# BottleBuddy-V1_2.net
KiCad netlist of a schematic drawn in EAGLE
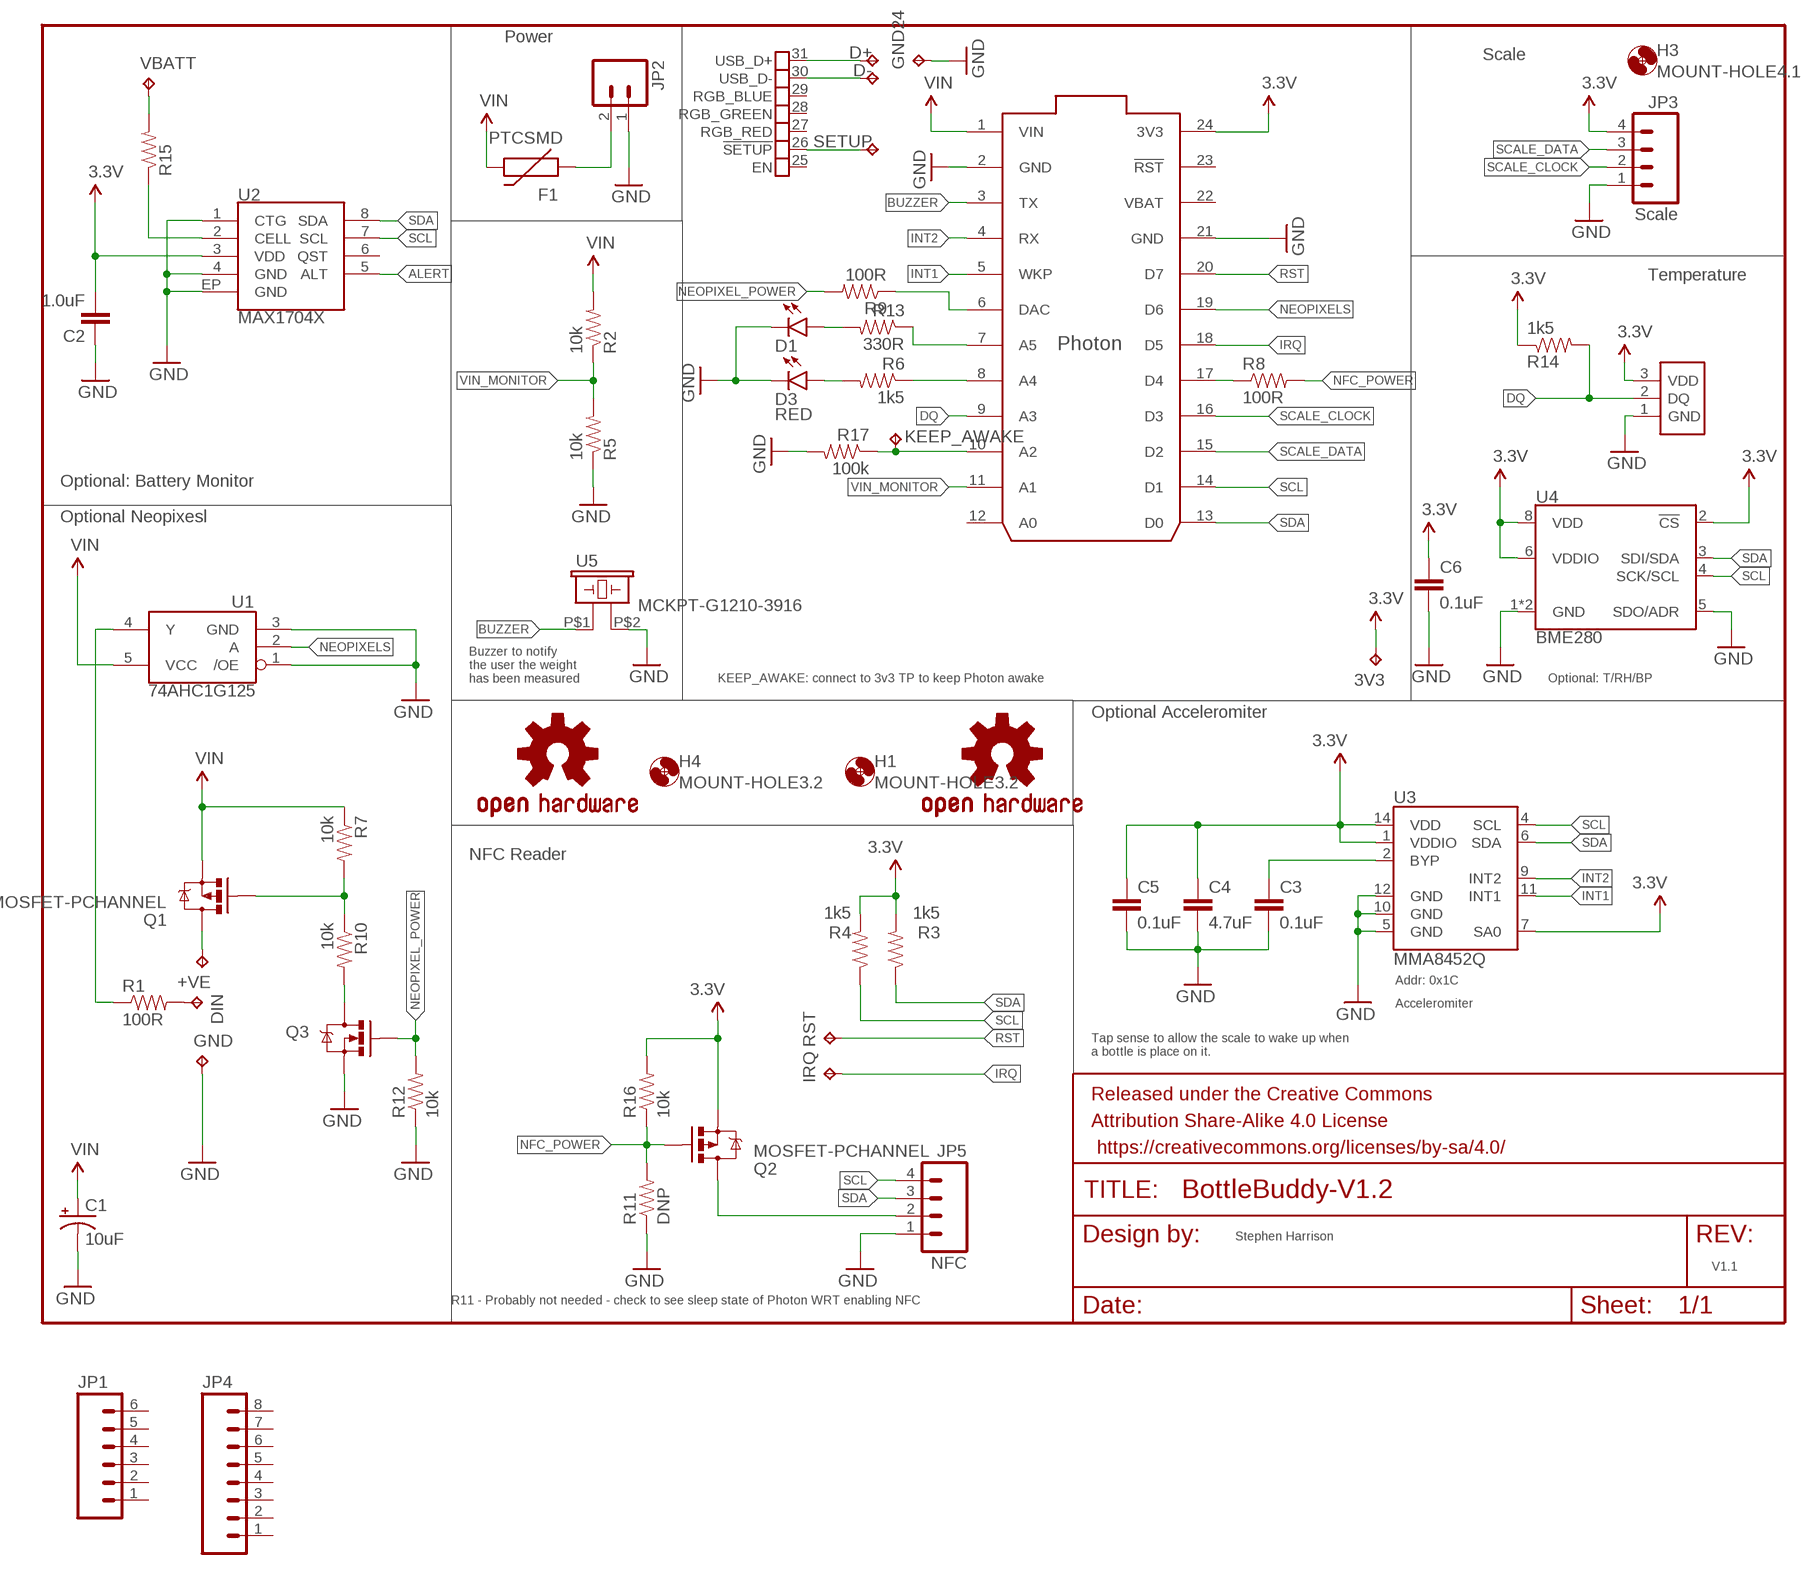
[diagram p0: schematic, sheet 1]

(export (version "E")
  (design (tool "Eeschema 10.0.6"))
  (components
    (comp (ref "+VE")
      (value "TPTP20R")
      (footprint "eagle-import:TP20R")
      (libsource (lib "eagle-import") (part "TPTP20R"))
    )
    (comp (ref "3V3")
      (value "TPTP20R")
      (footprint "eagle-import:TP20R")
      (libsource (lib "eagle-import") (part "TPTP20R"))
    )
    (comp (ref "C1")
      (value "10uF")
      (footprint "eagle-import:EIA3216")
      (libsource (lib "eagle-import") (part "10UF-16V-10%(TANT)"))
    )
    (comp (ref "C2")
      (value "1.0uF")
      (footprint "eagle-import:0805-CAP")
      (libsource (lib "eagle-import") (part "1.0UF-25V-+80/-20(0805){dblquote}"))
    )
    (comp (ref "C3")
      (value "0.1uF")
      (footprint "eagle-import:0805")
      (libsource (lib "eagle-import") (part "CAP0805"))
    )
    (comp (ref "C4")
      (value "4.7uF")
      (footprint "eagle-import:0805")
      (libsource (lib "eagle-import") (part "CAP0805"))
    )
    (comp (ref "C5")
      (value "0.1uF")
      (footprint "eagle-import:0805")
      (libsource (lib "eagle-import") (part "CAP0805"))
    )
    (comp (ref "C6")
      (value "0.1uF")
      (footprint "eagle-import:0805")
      (libsource (lib "eagle-import") (part "CAP0805"))
    )
    (comp (ref "D+")
      (value "TPTP20R")
      (footprint "eagle-import:TP20R")
      (libsource (lib "eagle-import") (part "TPTP20R"))
    )
    (comp (ref "D-")
      (value "TPTP20R")
      (footprint "eagle-import:TP20R")
      (libsource (lib "eagle-import") (part "TPTP20R"))
    )
    (comp (ref "D1")
      (value "LED1206-BOTTOM")
      (footprint "eagle-import:LED-1206-BOTTOM")
      (libsource (lib "eagle-import") (part "LED1206-BOTTOM"))
    )
    (comp (ref "D3")
      (value "RED")
      (footprint "eagle-import:LED-1206")
      (libsource (lib "eagle-import") (part "LED1206"))
    )
    (comp (ref "DIN")
      (value "TPTP20R")
      (footprint "eagle-import:TP20R")
      (libsource (lib "eagle-import") (part "TPTP20R"))
    )
    (comp (ref "F1")
      (value "PTCSMD")
      (footprint "eagle-import:PTC-1206")
      (libsource (lib "eagle-import") (part "PTCSMD"))
    )
    (comp (ref "FRAME1")
      (value "FRAME-LETTER")
      (footprint "eagle-import:CREATIVE_COMMONS")
      (libsource (lib "eagle-import") (part "FRAME-LETTER"))
    )
    (comp (ref "GND")
      (value "TPTP20R")
      (footprint "eagle-import:TP20R")
      (libsource (lib "eagle-import") (part "TPTP20R"))
    )
    (comp (ref "GND24")
      (value "TPTP20R")
      (footprint "eagle-import:TP20R")
      (libsource (lib "eagle-import") (part "TPTP20R"))
    )
    (comp (ref "H1")
      (value "MOUNT-HOLE3.2")
      (footprint "eagle-import:3,2")
      (libsource (lib "eagle-import") (part "MOUNT-HOLE3.2"))
    )
    (comp (ref "H3")
      (value "MOUNT-HOLE4.1")
      (footprint "eagle-import:4,1")
      (libsource (lib "eagle-import") (part "MOUNT-HOLE4.1"))
    )
    (comp (ref "H4")
      (value "MOUNT-HOLE3.2")
      (footprint "eagle-import:3,2")
      (libsource (lib "eagle-import") (part "MOUNT-HOLE3.2"))
    )
    (comp (ref "IRQ")
      (value "NFC IRQ")
      (footprint "eagle-import:TP20R")
      (libsource (lib "eagle-import") (part "TPTP20R"))
    )
    (comp (ref "JP1")
      (value "M06SILK_FEMALE_PTH")
      (footprint "eagle-import:1X06")
      (libsource (lib "eagle-import") (part "M06SILK_FEMALE_PTH"))
    )
    (comp (ref "JP2")
      (value "M02-JST-2MM-SMT")
      (footprint "eagle-import:JST-2-SMD")
      (libsource (lib "eagle-import") (part "M02-JST-2MM-SMT"))
    )
    (comp (ref "JP3")
      (value "Scale")
      (footprint "eagle-import:1X04")
      (libsource (lib "eagle-import") (part "M04PTH"))
    )
    (comp (ref "JP4")
      (value "M08SILK_FEMALE_PTH")
      (footprint "eagle-import:1X08")
      (libsource (lib "eagle-import") (part "M08SILK_FEMALE_PTH"))
    )
    (comp (ref "JP5")
      (value "NFC")
      (footprint "eagle-import:1X04")
      (libsource (lib "eagle-import") (part "M04PTH"))
    )
    (comp (ref "KEEP_AWAKE")
      (value "TPTP20R")
      (footprint "eagle-import:TP20R")
      (libsource (lib "eagle-import") (part "TPTP20R"))
    )
    (comp (ref "LOGO1")
      (value "OSHW-LOGOL")
      (footprint "eagle-import:OSHW-LOGO-L")
      (libsource (lib "eagle-import") (part "OSHW-LOGOL"))
    )
    (comp (ref "LOGO2")
      (value "OSHW-LOGOL")
      (footprint "eagle-import:OSHW-LOGO-L")
      (libsource (lib "eagle-import") (part "OSHW-LOGOL"))
    )
    (comp (ref "Q1")
      (value "MOSFET-PCHANNEL")
      (footprint "eagle-import:SOT23-3")
      (libsource (lib "eagle-import") (part "MOSFET-PCHANNEL"))
    )
    (comp (ref "Q2")
      (value "MOSFET-PCHANNEL")
      (footprint "eagle-import:SOT23-3")
      (libsource (lib "eagle-import") (part "MOSFET-PCHANNEL"))
    )
    (comp (ref "Q3")
      (value "200mA/50V")
      (footprint "eagle-import:SOT23-3")
      (libsource (lib "eagle-import") (part "MOSFET-NCHANNELBSS138"))
    )
    (comp (ref "R1")
      (value "100R")
      (footprint "eagle-import:1206")
      (libsource (lib "eagle-import") (part "RESISTOR1206"))
    )
    (comp (ref "R2")
      (value "10k")
      (footprint "eagle-import:1206")
      (libsource (lib "eagle-import") (part "RESISTOR1206"))
    )
    (comp (ref "R3")
      (value "1k5")
      (footprint "eagle-import:1206")
      (libsource (lib "eagle-import") (part "RESISTOR1206"))
    )
    (comp (ref "R4")
      (value "1k5")
      (footprint "eagle-import:1206")
      (libsource (lib "eagle-import") (part "RESISTOR1206"))
    )
    (comp (ref "R5")
      (value "10k")
      (footprint "eagle-import:1206")
      (libsource (lib "eagle-import") (part "RESISTOR1206"))
    )
    (comp (ref "R6")
      (value "1k5")
      (footprint "eagle-import:1206")
      (libsource (lib "eagle-import") (part "RESISTOR1206"))
    )
    (comp (ref "R7")
      (value "10k")
      (footprint "eagle-import:1206")
      (libsource (lib "eagle-import") (part "RESISTOR1206"))
    )
    (comp (ref "R8")
      (value "100R")
      (footprint "eagle-import:1206")
      (libsource (lib "eagle-import") (part "RESISTOR1206"))
    )
    (comp (ref "R9")
      (value "100R")
      (footprint "eagle-import:1206")
      (libsource (lib "eagle-import") (part "RESISTOR1206"))
    )
    (comp (ref "R10")
      (value "10k")
      (footprint "eagle-import:1206")
      (libsource (lib "eagle-import") (part "RESISTOR1206"))
    )
    (comp (ref "R11")
      (value "DNP")
      (footprint "eagle-import:1206")
      (libsource (lib "eagle-import") (part "RESISTOR1206"))
    )
    (comp (ref "R12")
      (value "10k")
      (footprint "eagle-import:1206")
      (libsource (lib "eagle-import") (part "RESISTOR1206"))
    )
    (comp (ref "R13")
      (value "330R")
      (footprint "eagle-import:1206")
      (libsource (lib "eagle-import") (part "RESISTOR1206"))
    )
    (comp (ref "R14")
      (value "1k5")
      (footprint "eagle-import:1206")
      (libsource (lib "eagle-import") (part "RESISTOR1206"))
    )
    (comp (ref "R15")
      (value "RESISTOR1206")
      (footprint "eagle-import:1206")
      (libsource (lib "eagle-import") (part "RESISTOR1206"))
    )
    (comp (ref "R16")
      (value "10k")
      (footprint "eagle-import:1206")
      (libsource (lib "eagle-import") (part "RESISTOR1206"))
    )
    (comp (ref "R17")
      (value "100k")
      (footprint "eagle-import:1206")
      (libsource (lib "eagle-import") (part "RESISTOR1206"))
    )
    (comp (ref "RST")
      (value "TPTP20R")
      (footprint "eagle-import:TP20R")
      (libsource (lib "eagle-import") (part "TPTP20R"))
    )
    (comp (ref "S1")
      (value "SENSOR-DS18B20")
      (footprint "eagle-import:TO-92-TRIANGLE")
      (libsource (lib "eagle-import") (part "SENSOR-DS18B20"))
    )
    (comp (ref "SETUP")
      (value "TPTP20R")
      (footprint "eagle-import:TP20R")
      (libsource (lib "eagle-import") (part "TPTP20R"))
    )
    (comp (ref "U$1")
      (value "PHOTON_SMD")
      (footprint "eagle-import:PHOTON_SMD")
      (libsource (lib "eagle-import") (part "PHOTON_SMD"))
    )
    (comp (ref "U1")
      (value "74AHC1G125")
      (footprint "eagle-import:SOT23-5")
      (libsource (lib "eagle-import") (part "74AHC1G125"))
    )
    (comp (ref "U2")
      (value "MAX1704X")
      (footprint "eagle-import:TDFN-8")
      (libsource (lib "eagle-import") (part "MAX1704X"))
    )
    (comp (ref "U3")
      (value "MMA8452Q")
      (footprint "eagle-import:QFN-16_0.5MM")
      (libsource (lib "eagle-import") (part "MMA8452Q"))
    )
    (comp (ref "U4")
      (value "BME280")
      (footprint "eagle-import:LGA-8-2.5X2.5")
      (libsource (lib "eagle-import") (part "BME280"))
    )
    (comp (ref "U5")
      (value "MCKPT-G1210-3916")
      (footprint "eagle-import:BUZZER-12MM")
      (libsource (lib "eagle-import") (part "MCKPT-G1210-3916"))
    )
    (comp (ref "VBATT")
      (value "TPTP20R")
      (footprint "eagle-import:TP20R")
      (libsource (lib "eagle-import") (part "TPTP20R"))
    )
  )
  (nets
    (net (code "1") (name "/VBAT") (class "Default")
      (node (ref "U$1") (pin "22") (pinfunction "VBAT_22") (pintype "power_in"))
    )
    (net (code "2") (name "3.3V") (class "Default")
      (node (ref "3V3") (pin "TP") (pinfunction "TP_TP") (pintype "input"))
      (node (ref "C2") (pin "2") (pinfunction "2_2") (pintype "passive"))
      (node (ref "C4") (pin "1") (pinfunction "1_1") (pintype "passive"))
      (node (ref "C5") (pin "1") (pinfunction "1_1") (pintype "passive"))
      (node (ref "C6") (pin "1") (pinfunction "1_1") (pintype "passive"))
      (node (ref "JP3") (pin "4") (pinfunction "4_4") (pintype "passive"))
      (node (ref "Q2") (pin "2") (pinfunction "S_2") (pintype "passive"))
      (node (ref "R14") (pin "1") (pinfunction "1_1") (pintype "passive"))
      (node (ref "R16") (pin "2") (pinfunction "2_2") (pintype "passive"))
      (node (ref "R3") (pin "2") (pinfunction "2_2") (pintype "passive"))
      (node (ref "R4") (pin "2") (pinfunction "2_2") (pintype "passive"))
      (node (ref "S1") (pin "3") (pinfunction "VDD_3") (pintype "bidirectional"))
      (node (ref "U$1") (pin "24") (pinfunction "3V3_24") (pintype "power_in"))
      (node (ref "U2") (pin "3") (pinfunction "VDD_3") (pintype "bidirectional"))
      (node (ref "U3") (pin "1") (pinfunction "VDDIO_1") (pintype "bidirectional"))
      (node (ref "U3") (pin "14") (pinfunction "VDD_14") (pintype "bidirectional"))
      (node (ref "U3") (pin "7") (pinfunction "SA0_7") (pintype "bidirectional"))
      (node (ref "U4") (pin "2") (pinfunction "~{CS}_2") (pintype "bidirectional"))
      (node (ref "U4") (pin "6") (pinfunction "VDDIO_6") (pintype "bidirectional"))
      (node (ref "U4") (pin "8") (pinfunction "VDD_8") (pintype "bidirectional"))
    )
    (net (code "3") (name "ALERT") (class "Default")
      (node (ref "U2") (pin "5") (pinfunction "ALT_5") (pintype "bidirectional"))
    )
    (net (code "4") (name "BUZZER") (class "Default")
      (node (ref "U$1") (pin "3") (pinfunction "TX_3") (pintype "bidirectional"))
      (node (ref "U5") (pin "P$1") (pinfunction "1_P$1") (pintype "passive"))
    )
    (net (code "5") (name "DQ") (class "Default")
      (node (ref "R14") (pin "2") (pinfunction "2_2") (pintype "passive"))
      (node (ref "S1") (pin "2") (pinfunction "DQ_2") (pintype "bidirectional"))
      (node (ref "U$1") (pin "9") (pinfunction "A3_9") (pintype "bidirectional"))
    )
    (net (code "6") (name "GND") (class "Default")
      (node (ref "C1") (pin "C") (pinfunction "-_C") (pintype "passive"))
      (node (ref "C2") (pin "1") (pinfunction "1_1") (pintype "passive"))
      (node (ref "C3") (pin "2") (pinfunction "2_2") (pintype "passive"))
      (node (ref "C4") (pin "2") (pinfunction "2_2") (pintype "passive"))
      (node (ref "C5") (pin "2") (pinfunction "2_2") (pintype "passive"))
      (node (ref "C6") (pin "2") (pinfunction "2_2") (pintype "passive"))
      (node (ref "D1") (pin "C") (pinfunction "C_C") (pintype "passive"))
      (node (ref "D3") (pin "C") (pinfunction "C_C") (pintype "passive"))
      (node (ref "GND") (pin "TP") (pinfunction "TP_TP") (pintype "input"))
      (node (ref "GND24") (pin "TP") (pinfunction "TP_TP") (pintype "input"))
      (node (ref "JP2") (pin "1") (pinfunction "2_1") (pintype "passive"))
      (node (ref "JP3") (pin "1") (pinfunction "1_1") (pintype "passive"))
      (node (ref "JP5") (pin "1") (pinfunction "1_1") (pintype "passive"))
      (node (ref "Q3") (pin "2") (pinfunction "S_2") (pintype "passive"))
      (node (ref "R11") (pin "1") (pinfunction "1_1") (pintype "passive"))
      (node (ref "R12") (pin "1") (pinfunction "1_1") (pintype "passive"))
      (node (ref "R17") (pin "2") (pinfunction "2_2") (pintype "passive"))
      (node (ref "R5") (pin "1") (pinfunction "1_1") (pintype "passive"))
      (node (ref "S1") (pin "1") (pinfunction "GND_1") (pintype "bidirectional"))
      (node (ref "U$1") (pin "2") (pinfunction "GND_2") (pintype "power_in"))
      (node (ref "U$1") (pin "21") (pinfunction "GND_21") (pintype "power_in"))
      (node (ref "U1") (pin "1") (pinfunction "/OE_1") (pintype "bidirectional"))
      (node (ref "U1") (pin "3") (pinfunction "GND_3") (pintype "bidirectional"))
      (node (ref "U2") (pin "1") (pinfunction "CTG_1") (pintype "bidirectional"))
      (node (ref "U2") (pin "4") (pinfunction "GND_4") (pintype "bidirectional"))
      (node (ref "U2") (pin "EP") (pinfunction "GND_EP") (pintype "bidirectional"))
      (node (ref "U3") (pin "10") (pinfunction "GND_10") (pintype "bidirectional"))
      (node (ref "U3") (pin "12") (pinfunction "GND_12") (pintype "bidirectional"))
      (node (ref "U3") (pin "5") (pinfunction "GND_5") (pintype "bidirectional"))
      (node (ref "U4") (pin "1") (pinfunction "GND_1") (pintype "bidirectional"))
      (node (ref "U4") (pin "5") (pinfunction "SDO/ADR_5") (pintype "bidirectional"))
      (node (ref "U4") (pin "7") (pinfunction "GND_7") (pintype "bidirectional"))
      (node (ref "U5") (pin "P$2") (pinfunction "2_P$2") (pintype "passive"))
    )
    (net (code "7") (name "INT1") (class "Default")
      (node (ref "U$1") (pin "5") (pinfunction "WKP_5") (pintype "bidirectional"))
      (node (ref "U3") (pin "11") (pinfunction "INT1_11") (pintype "bidirectional"))
    )
    (net (code "8") (name "INT2") (class "Default")
      (node (ref "U$1") (pin "4") (pinfunction "RX_4") (pintype "bidirectional"))
      (node (ref "U3") (pin "9") (pinfunction "INT2_9") (pintype "bidirectional"))
    )
    (net (code "9") (name "IRQ") (class "Default")
      (node (ref "IRQ") (pin "TP") (pinfunction "TP_TP") (pintype "input"))
      (node (ref "U$1") (pin "18") (pinfunction "D5_18") (pintype "bidirectional"))
    )
    (net (code "10") (name "NEOPIXELS") (class "Default")
      (node (ref "U$1") (pin "19") (pinfunction "D6_19") (pintype "bidirectional"))
      (node (ref "U1") (pin "2") (pinfunction "A_2") (pintype "bidirectional"))
    )
    (net (code "11") (name "NEOPIXEL_POWER") (class "Default")
      (node (ref "Q3") (pin "1") (pinfunction "G_1") (pintype "passive"))
      (node (ref "R12") (pin "2") (pinfunction "2_2") (pintype "passive"))
      (node (ref "R9") (pin "2") (pinfunction "2_2") (pintype "passive"))
    )
    (net (code "12") (name "NFC_POWER") (class "Default")
      (node (ref "Q2") (pin "1") (pinfunction "G_1") (pintype "passive"))
      (node (ref "R11") (pin "2") (pinfunction "2_2") (pintype "passive"))
      (node (ref "R16") (pin "1") (pinfunction "1_1") (pintype "passive"))
      (node (ref "R8") (pin "2") (pinfunction "2_2") (pintype "passive"))
    )
    (net (code "13") (name "Net-(D1-PadA)") (class "Default")
      (node (ref "D1") (pin "A") (pinfunction "A_A") (pintype "passive"))
      (node (ref "R13") (pin "2") (pinfunction "2_2") (pintype "passive"))
    )
    (net (code "14") (name "Net-(D3-PadA)") (class "Default")
      (node (ref "D3") (pin "A") (pinfunction "A_A") (pintype "passive"))
      (node (ref "R6") (pin "2") (pinfunction "2_2") (pintype "passive"))
    )
    (net (code "15") (name "Net-(DIN-PadTP)") (class "Default")
      (node (ref "DIN") (pin "TP") (pinfunction "TP_TP") (pintype "input"))
      (node (ref "R1") (pin "2") (pinfunction "2_2") (pintype "passive"))
    )
    (net (code "16") (name "Net-(JP2-1)") (class "Default")
      (node (ref "F1") (pin "1") (pinfunction "1_1") (pintype "bidirectional"))
      (node (ref "JP2") (pin "2") (pinfunction "1_2") (pintype "passive"))
    )
    (net (code "17") (name "Net-(Q1-D)") (class "Default")
      (node (ref "+VE") (pin "TP") (pinfunction "TP_TP") (pintype "input"))
      (node (ref "Q1") (pin "3") (pinfunction "D_3") (pintype "passive"))
    )
    (net (code "18") (name "Net-(Q1-G)") (class "Default")
      (node (ref "Q1") (pin "1") (pinfunction "G_1") (pintype "passive"))
      (node (ref "R10") (pin "1") (pinfunction "1_1") (pintype "passive"))
      (node (ref "R7") (pin "2") (pinfunction "2_2") (pintype "passive"))
    )
    (net (code "19") (name "Net-(Q2-D)") (class "Default")
      (node (ref "JP5") (pin "2") (pinfunction "2_2") (pintype "passive"))
      (node (ref "Q2") (pin "3") (pinfunction "D_3") (pintype "passive"))
    )
    (net (code "20") (name "Net-(Q3-D)") (class "Default")
      (node (ref "Q3") (pin "3") (pinfunction "D_3") (pintype "passive"))
      (node (ref "R10") (pin "2") (pinfunction "2_2") (pintype "passive"))
    )
    (net (code "21") (name "Net-(R15-Pad2)") (class "Default")
      (node (ref "R15") (pin "2") (pinfunction "2_2") (pintype "passive"))
      (node (ref "VBATT") (pin "TP") (pinfunction "TP_TP") (pintype "input"))
    )
    (net (code "22") (name "Net-(U$1A-A2)") (class "Default")
      (node (ref "KEEP_AWAKE") (pin "TP") (pinfunction "TP_TP") (pintype "input"))
      (node (ref "R17") (pin "1") (pinfunction "1_1") (pintype "passive"))
      (node (ref "U$1") (pin "10") (pinfunction "A2_10") (pintype "bidirectional"))
    )
    (net (code "23") (name "Net-(U$1A-A4)") (class "Default")
      (node (ref "R6") (pin "1") (pinfunction "1_1") (pintype "passive"))
      (node (ref "U$1") (pin "8") (pinfunction "A4_8") (pintype "bidirectional"))
    )
    (net (code "24") (name "Net-(U$1A-A5)") (class "Default")
      (node (ref "R13") (pin "1") (pinfunction "1_1") (pintype "passive"))
      (node (ref "U$1") (pin "7") (pinfunction "A5_7") (pintype "bidirectional"))
    )
    (net (code "25") (name "Net-(U$1A-D4)") (class "Default")
      (node (ref "R8") (pin "1") (pinfunction "1_1") (pintype "passive"))
      (node (ref "U$1") (pin "17") (pinfunction "D4_17") (pintype "bidirectional"))
    )
    (net (code "26") (name "Net-(U$1A-DAC)") (class "Default")
      (node (ref "R9") (pin "1") (pinfunction "1_1") (pintype "passive"))
      (node (ref "U$1") (pin "6") (pinfunction "DAC_6") (pintype "bidirectional"))
    )
    (net (code "27") (name "Net-(U$1B-USB_D+)") (class "Default")
      (node (ref "D+") (pin "TP") (pinfunction "TP_TP") (pintype "input"))
      (node (ref "U$1") (pin "31") (pinfunction "USB_D+_31") (pintype "bidirectional"))
    )
    (net (code "28") (name "Net-(U$1B-USB_D-)") (class "Default")
      (node (ref "D-") (pin "TP") (pinfunction "TP_TP") (pintype "input"))
      (node (ref "U$1") (pin "30") (pinfunction "USB_D-_30") (pintype "bidirectional"))
    )
    (net (code "29") (name "Net-(U$1B-~{SETUP})") (class "Default")
      (node (ref "SETUP") (pin "TP") (pinfunction "TP_TP") (pintype "input"))
      (node (ref "U$1") (pin "26") (pinfunction "~{SETUP}_26") (pintype "bidirectional"))
    )
    (net (code "30") (name "Net-(U1-Y)") (class "Default")
      (node (ref "R1") (pin "1") (pinfunction "1_1") (pintype "passive"))
      (node (ref "U1") (pin "4") (pinfunction "Y_4") (pintype "bidirectional"))
    )
    (net (code "31") (name "Net-(U2-CELL)") (class "Default")
      (node (ref "R15") (pin "1") (pinfunction "1_1") (pintype "passive"))
      (node (ref "U2") (pin "2") (pinfunction "CELL_2") (pintype "bidirectional"))
    )
    (net (code "32") (name "Net-(U3-BYP)") (class "Default")
      (node (ref "C3") (pin "1") (pinfunction "1_1") (pintype "passive"))
      (node (ref "U3") (pin "2") (pinfunction "BYP_2") (pintype "bidirectional"))
    )
    (net (code "33") (name "RST") (class "Default")
      (node (ref "RST") (pin "TP") (pinfunction "TP_TP") (pintype "input"))
      (node (ref "U$1") (pin "20") (pinfunction "D7_20") (pintype "bidirectional"))
    )
    (net (code "34") (name "SCALE_CLOCK") (class "Default")
      (node (ref "JP3") (pin "2") (pinfunction "2_2") (pintype "passive"))
      (node (ref "U$1") (pin "16") (pinfunction "D3_16") (pintype "bidirectional"))
    )
    (net (code "35") (name "SCALE_DATA") (class "Default")
      (node (ref "JP3") (pin "3") (pinfunction "3_3") (pintype "passive"))
      (node (ref "U$1") (pin "15") (pinfunction "D2_15") (pintype "bidirectional"))
    )
    (net (code "36") (name "SCL") (class "Default")
      (node (ref "JP5") (pin "4") (pinfunction "4_4") (pintype "passive"))
      (node (ref "R4") (pin "1") (pinfunction "1_1") (pintype "passive"))
      (node (ref "U$1") (pin "14") (pinfunction "D1_14") (pintype "bidirectional"))
      (node (ref "U2") (pin "7") (pinfunction "SCL_7") (pintype "bidirectional"))
      (node (ref "U3") (pin "4") (pinfunction "SCL_4") (pintype "bidirectional"))
      (node (ref "U4") (pin "4") (pinfunction "SCK/SCL_4") (pintype "bidirectional"))
    )
    (net (code "37") (name "SDA") (class "Default")
      (node (ref "JP5") (pin "3") (pinfunction "3_3") (pintype "passive"))
      (node (ref "R3") (pin "1") (pinfunction "1_1") (pintype "passive"))
      (node (ref "U$1") (pin "13") (pinfunction "D0_13") (pintype "bidirectional"))
      (node (ref "U2") (pin "8") (pinfunction "SDA_8") (pintype "bidirectional"))
      (node (ref "U3") (pin "6") (pinfunction "SDA_6") (pintype "bidirectional"))
      (node (ref "U4") (pin "3") (pinfunction "SDI/SDA_3") (pintype "bidirectional"))
    )
    (net (code "38") (name "VIN") (class "Default")
      (node (ref "C1") (pin "A") (pinfunction "+_A") (pintype "passive"))
      (node (ref "F1") (pin "2") (pinfunction "2_2") (pintype "bidirectional"))
      (node (ref "Q1") (pin "2") (pinfunction "S_2") (pintype "passive"))
      (node (ref "R2") (pin "2") (pinfunction "2_2") (pintype "passive"))
      (node (ref "R7") (pin "1") (pinfunction "1_1") (pintype "passive"))
      (node (ref "U$1") (pin "1") (pinfunction "VIN_1") (pintype "power_in"))
      (node (ref "U1") (pin "5") (pinfunction "VCC_5") (pintype "bidirectional"))
    )
    (net (code "39") (name "VIN_MONITOR") (class "Default")
      (node (ref "R2") (pin "1") (pinfunction "1_1") (pintype "passive"))
      (node (ref "R5") (pin "2") (pinfunction "2_2") (pintype "passive"))
      (node (ref "U$1") (pin "11") (pinfunction "A1_11") (pintype "bidirectional"))
    )
    (net (code "40") (name "unconnected-(JP1-Pad1)") (class "Default")
      (node (ref "JP1") (pin "1") (pinfunction "1_1") (pintype "passive"))
    )
    (net (code "41") (name "unconnected-(JP1-Pad2)") (class "Default")
      (node (ref "JP1") (pin "2") (pinfunction "2_2") (pintype "passive"))
    )
    (net (code "42") (name "unconnected-(JP1-Pad3)") (class "Default")
      (node (ref "JP1") (pin "3") (pinfunction "3_3") (pintype "passive"))
    )
    (net (code "43") (name "unconnected-(JP1-Pad4)") (class "Default")
      (node (ref "JP1") (pin "4") (pinfunction "4_4") (pintype "passive"))
    )
    (net (code "44") (name "unconnected-(JP1-Pad5)") (class "Default")
      (node (ref "JP1") (pin "5") (pinfunction "5_5") (pintype "passive"))
    )
    (net (code "45") (name "unconnected-(JP1-Pad6)") (class "Default")
      (node (ref "JP1") (pin "6") (pinfunction "6_6") (pintype "passive"))
    )
    (net (code "46") (name "unconnected-(JP4-Pad1)") (class "Default")
      (node (ref "JP4") (pin "1") (pinfunction "1_1") (pintype "passive"))
    )
    (net (code "47") (name "unconnected-(JP4-Pad2)") (class "Default")
      (node (ref "JP4") (pin "2") (pinfunction "2_2") (pintype "passive"))
    )
    (net (code "48") (name "unconnected-(JP4-Pad3)") (class "Default")
      (node (ref "JP4") (pin "3") (pinfunction "3_3") (pintype "passive"))
    )
    (net (code "49") (name "unconnected-(JP4-Pad4)") (class "Default")
      (node (ref "JP4") (pin "4") (pinfunction "4_4") (pintype "passive"))
    )
    (net (code "50") (name "unconnected-(JP4-Pad5)") (class "Default")
      (node (ref "JP4") (pin "5") (pinfunction "5_5") (pintype "passive"))
    )
    (net (code "51") (name "unconnected-(JP4-Pad6)") (class "Default")
      (node (ref "JP4") (pin "6") (pinfunction "6_6") (pintype "passive"))
    )
    (net (code "52") (name "unconnected-(JP4-Pad7)") (class "Default")
      (node (ref "JP4") (pin "7") (pinfunction "7_7") (pintype "passive"))
    )
    (net (code "53") (name "unconnected-(JP4-Pad8)") (class "Default")
      (node (ref "JP4") (pin "8") (pinfunction "8_8") (pintype "passive"))
    )
    (net (code "54") (name "unconnected-(U$1A-A0-Pad12)") (class "Default")
      (node (ref "U$1") (pin "12") (pinfunction "A0_12") (pintype "bidirectional"))
    )
    (net (code "55") (name "unconnected-(U$1A-~{RST}-Pad23)") (class "Default")
      (node (ref "U$1") (pin "23") (pinfunction "~{RST}_23") (pintype "bidirectional"))
    )
    (net (code "56") (name "unconnected-(U$1B-EN-Pad25)") (class "Default")
      (node (ref "U$1") (pin "25") (pinfunction "EN_25") (pintype "bidirectional"))
    )
    (net (code "57") (name "unconnected-(U$1B-RGB_BLUE-Pad29)") (class "Default")
      (node (ref "U$1") (pin "29") (pinfunction "RGB_BLUE_29") (pintype "bidirectional"))
    )
    (net (code "58") (name "unconnected-(U$1B-RGB_GREEN-Pad28)") (class "Default")
      (node (ref "U$1") (pin "28") (pinfunction "RGB_GREEN_28") (pintype "bidirectional"))
    )
    (net (code "59") (name "unconnected-(U$1B-RGB_RED-Pad27)") (class "Default")
      (node (ref "U$1") (pin "27") (pinfunction "RGB_RED_27") (pintype "bidirectional"))
    )
    (net (code "60") (name "unconnected-(U2-QST-Pad6)") (class "Default")
      (node (ref "U2") (pin "6") (pinfunction "QST_6") (pintype "bidirectional"))
    )
  )
)
